# Power_Alert.net
KiCad netlist of a schematic drawn in EAGLE
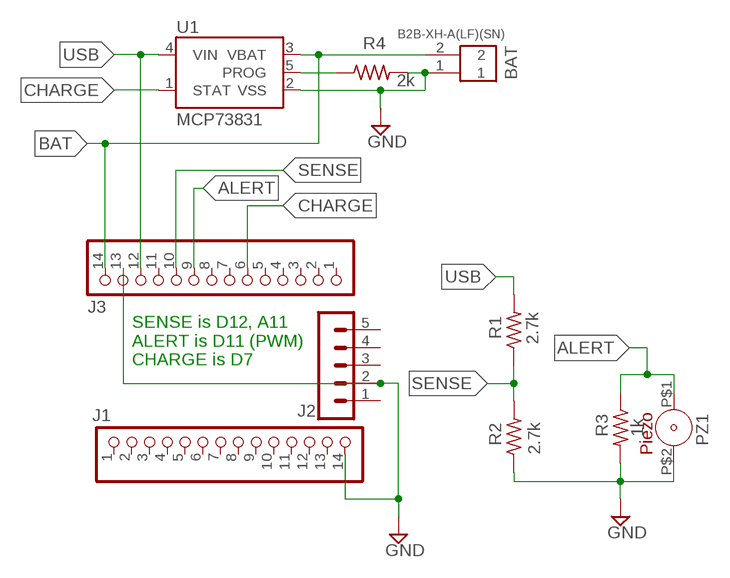
[diagram p0: schematic, sheet 1]

(export (version "E")
  (design (tool "Eeschema 10.0.6"))
  (components
    (comp (ref "BAT")
      (value "B2B-XH-A(LF)(SN)")
      (footprint "eagle-import:B2B-XH-A(LF)(SN)")
      (fields
        (field (name "DIGIKEY_PARTNO") "455-2249-ND")
        (field (name "MANUFACTURER") "JST Sales America Inc.")
        (field (name "MPN") "B4B-XH-A(LF)(SN)")
        (field (name "CREATED_BY") "PCBLayout.com")
      )
      (libsource (lib "eagle-import") (part "B2B-XH-A(LF)(SN)"))
    )
    (comp (ref "J1")
      (value "PINHD-1X14")
      (footprint "eagle-import:1X14")
      (libsource (lib "eagle-import") (part "PINHD-1X14"))
    )
    (comp (ref "J2")
      (value "MA05-1")
      (footprint "eagle-import:MA05-1")
      (libsource (lib "eagle-import") (part "MA05-1"))
    )
    (comp (ref "J3")
      (value "PINHD-1X14")
      (footprint "eagle-import:1X14")
      (libsource (lib "eagle-import") (part "PINHD-1X14"))
    )
    (comp (ref "PZ1")
      (value "TDK-PS1420P02CT")
      (footprint "eagle-import:TDK-PS1420P02CT")
      (libsource (lib "eagle-import") (part "TDK-PS1420P02CT"))
    )
    (comp (ref "R1")
      (value "2.7k")
      (footprint "eagle-import:R1206")
      (libsource (lib "eagle-import") (part "R-US_R1206"))
    )
    (comp (ref "R2")
      (value "2.7k")
      (footprint "eagle-import:R1206")
      (libsource (lib "eagle-import") (part "R-US_R1206"))
    )
    (comp (ref "R3")
      (value "1k")
      (footprint "eagle-import:R1206")
      (libsource (lib "eagle-import") (part "R-US_R1206"))
    )
    (comp (ref "R4")
      (value "2k")
      (footprint "eagle-import:M1206")
      (libsource (lib "eagle-import") (part "R-US_M1206"))
    )
    (comp (ref "U1")
      (value "MCP73831")
      (footprint "eagle-import:SOT23-5")
      (libsource (lib "eagle-import") (part "MCP73831"))
    )
  )
  (nets
    (net (code "1") (name "ALERT") (class "Default")
      (node (ref "J3") (pin "9") (pinfunction "9_9") (pintype "passive"))
      (node (ref "PZ1") (pin "P$1") (pinfunction "1_P$1") (pintype "passive"))
      (node (ref "R3") (pin "1") (pinfunction "1_1") (pintype "passive"))
    )
    (net (code "2") (name "BAT") (class "Default")
      (node (ref "BAT") (pin "2") (pinfunction "2_2") (pintype "passive"))
      (node (ref "J3") (pin "14") (pinfunction "14_14") (pintype "passive"))
      (node (ref "U1") (pin "3") (pinfunction "VBAT_3") (pintype "power_in"))
    )
    (net (code "3") (name "CHARGE") (class "Default")
      (node (ref "J3") (pin "6") (pinfunction "6_6") (pintype "passive"))
      (node (ref "U1") (pin "1") (pinfunction "STAT_1") (pintype "output"))
    )
    (net (code "4") (name "GND") (class "Default")
      (node (ref "BAT") (pin "1") (pinfunction "1_1") (pintype "passive"))
      (node (ref "J1") (pin "14") (pinfunction "14_14") (pintype "passive"))
      (node (ref "J2") (pin "2") (pinfunction "2_2") (pintype "passive"))
      (node (ref "J3") (pin "13") (pinfunction "13_13") (pintype "passive"))
      (node (ref "PZ1") (pin "P$2") (pinfunction "2_P$2") (pintype "passive"))
      (node (ref "R2") (pin "1") (pinfunction "1_1") (pintype "passive"))
      (node (ref "R3") (pin "2") (pinfunction "2_2") (pintype "passive"))
      (node (ref "R4") (pin "2") (pinfunction "2_2") (pintype "passive"))
      (node (ref "U1") (pin "2") (pinfunction "VSS_2") (pintype "power_in"))
    )
    (net (code "5") (name "Net-(U1-PROG)") (class "Default")
      (node (ref "R4") (pin "1") (pinfunction "1_1") (pintype "passive"))
      (node (ref "U1") (pin "5") (pinfunction "PROG_5") (pintype "input"))
    )
    (net (code "6") (name "SENSE") (class "Default")
      (node (ref "J3") (pin "10") (pinfunction "10_10") (pintype "passive"))
      (node (ref "R1") (pin "1") (pinfunction "1_1") (pintype "passive"))
      (node (ref "R2") (pin "2") (pinfunction "2_2") (pintype "passive"))
    )
    (net (code "7") (name "USB") (class "Default")
      (node (ref "J3") (pin "12") (pinfunction "12_12") (pintype "passive"))
      (node (ref "R1") (pin "2") (pinfunction "2_2") (pintype "passive"))
      (node (ref "U1") (pin "4") (pinfunction "VIN_4") (pintype "power_in"))
    )
    (net (code "8") (name "unconnected-(J1-Pad1)") (class "Default")
      (node (ref "J1") (pin "1") (pinfunction "1_1") (pintype "passive"))
    )
    (net (code "9") (name "unconnected-(J1-Pad2)") (class "Default")
      (node (ref "J1") (pin "2") (pinfunction "2_2") (pintype "passive"))
    )
    (net (code "10") (name "unconnected-(J1-Pad3)") (class "Default")
      (node (ref "J1") (pin "3") (pinfunction "3_3") (pintype "passive"))
    )
    (net (code "11") (name "unconnected-(J1-Pad4)") (class "Default")
      (node (ref "J1") (pin "4") (pinfunction "4_4") (pintype "passive"))
    )
    (net (code "12") (name "unconnected-(J1-Pad5)") (class "Default")
      (node (ref "J1") (pin "5") (pinfunction "5_5") (pintype "passive"))
    )
    (net (code "13") (name "unconnected-(J1-Pad6)") (class "Default")
      (node (ref "J1") (pin "6") (pinfunction "6_6") (pintype "passive"))
    )
    (net (code "14") (name "unconnected-(J1-Pad7)") (class "Default")
      (node (ref "J1") (pin "7") (pinfunction "7_7") (pintype "passive"))
    )
    (net (code "15") (name "unconnected-(J1-Pad8)") (class "Default")
      (node (ref "J1") (pin "8") (pinfunction "8_8") (pintype "passive"))
    )
    (net (code "16") (name "unconnected-(J1-Pad9)") (class "Default")
      (node (ref "J1") (pin "9") (pinfunction "9_9") (pintype "passive"))
    )
    (net (code "17") (name "unconnected-(J1-Pad10)") (class "Default")
      (node (ref "J1") (pin "10") (pinfunction "10_10") (pintype "passive"))
    )
    (net (code "18") (name "unconnected-(J1-Pad11)") (class "Default")
      (node (ref "J1") (pin "11") (pinfunction "11_11") (pintype "passive"))
    )
    (net (code "19") (name "unconnected-(J1-Pad12)") (class "Default")
      (node (ref "J1") (pin "12") (pinfunction "12_12") (pintype "passive"))
    )
    (net (code "20") (name "unconnected-(J1-Pad13)") (class "Default")
      (node (ref "J1") (pin "13") (pinfunction "13_13") (pintype "passive"))
    )
    (net (code "21") (name "unconnected-(J2-Pad1)") (class "Default")
      (node (ref "J2") (pin "1") (pinfunction "1_1") (pintype "passive"))
    )
    (net (code "22") (name "unconnected-(J2-Pad3)") (class "Default")
      (node (ref "J2") (pin "3") (pinfunction "3_3") (pintype "passive"))
    )
    (net (code "23") (name "unconnected-(J2-Pad4)") (class "Default")
      (node (ref "J2") (pin "4") (pinfunction "4_4") (pintype "passive"))
    )
    (net (code "24") (name "unconnected-(J2-Pad5)") (class "Default")
      (node (ref "J2") (pin "5") (pinfunction "5_5") (pintype "passive"))
    )
    (net (code "25") (name "unconnected-(J3-Pad1)") (class "Default")
      (node (ref "J3") (pin "1") (pinfunction "1_1") (pintype "passive"))
    )
    (net (code "26") (name "unconnected-(J3-Pad2)") (class "Default")
      (node (ref "J3") (pin "2") (pinfunction "2_2") (pintype "passive"))
    )
    (net (code "27") (name "unconnected-(J3-Pad3)") (class "Default")
      (node (ref "J3") (pin "3") (pinfunction "3_3") (pintype "passive"))
    )
    (net (code "28") (name "unconnected-(J3-Pad4)") (class "Default")
      (node (ref "J3") (pin "4") (pinfunction "4_4") (pintype "passive"))
    )
    (net (code "29") (name "unconnected-(J3-Pad5)") (class "Default")
      (node (ref "J3") (pin "5") (pinfunction "5_5") (pintype "passive"))
    )
    (net (code "30") (name "unconnected-(J3-Pad7)") (class "Default")
      (node (ref "J3") (pin "7") (pinfunction "7_7") (pintype "passive"))
    )
    (net (code "31") (name "unconnected-(J3-Pad8)") (class "Default")
      (node (ref "J3") (pin "8") (pinfunction "8_8") (pintype "passive"))
    )
    (net (code "32") (name "unconnected-(J3-Pad11)") (class "Default")
      (node (ref "J3") (pin "11") (pinfunction "11_11") (pintype "passive"))
    )
  )
)
